# CHARGER.net
KiCad netlist of a schematic drawn in Altium Designer
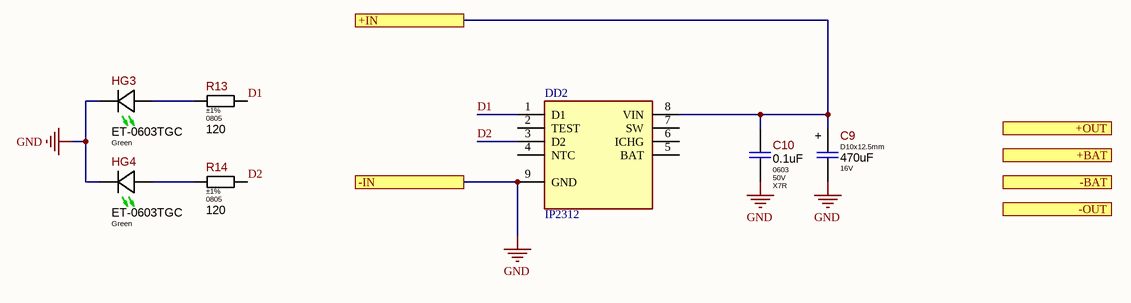
[diagram p0: CHARGER.SchDoc]

(export (version "E")
  (design (tool "Eeschema 10.0.6"))
  (components
    (comp (ref "C9")
      (value "470uF")
      (footprint "CAP-AE-PTH-100D10x125H15")
      (description "470uF 16V D10x12.5mm Electrolytic Low Impedance")
      (fields
        (field (name "PACKAGE") "D10x12.5mm")
        (field (name "VOLTAGE") "16V")
        (field (name "PART NUMBER") "EXR471M16B")
        (field (name "MANUFACTURER") "Hitano")
      )
      (libsource (lib "capacitors") (part "EXR471M16B"))
    )
    (comp (ref "C10")
      (value "0.1uF")
      (footprint "C_CERAMIC_0603_MED")
      (description "100nF 50V X7R ±10% 0603 Ceramic Capacitor RoHS")
      (fields
        (field (name "PACKAGE") "0603")
        (field (name "VOLTAGE") "50V")
        (field (name "DIELECTRIC TYPE") "X7R")
        (field (name "PART NUMBER") "CL10B104KB8NNND")
        (field (name "MANUFACTURER") "Samsung Electro-Mechanics")
      )
      (libsource (lib "capacitors") (part "CL10B104KB8NNND"))
    )
    (comp (ref "DD2") (value "IP2312") (footprint "IP2313") (libsource (lib "vitech_lib") (part "IP2312")))
    (comp (ref "HG3")
      (value "ET-0603TGC")
      (footprint "ET-0603")
      (description "Low Power LED, Green 525nm, SMD 0603, Vf 2.35V, 28.5 ~ 72mcd @ 20 mA, 120°")
      (fields
        (field (name "PART NUMBER") "ET-0603TGC")
        (field (name "COLOR") "Green")
        (field (name "MANUFACTURER") "Everlight Electronics")
      )
      (libsource (lib "opto") (part "ET-0603TGC"))
    )
    (comp (ref "HG4")
      (value "ET-0603TGC")
      (footprint "ET-0603")
      (description "Low Power LED, Green 525nm, SMD 0603, Vf 2.35V, 28.5 ~ 72mcd @ 20 mA, 120°")
      (fields
        (field (name "PART NUMBER") "ET-0603TGC")
        (field (name "COLOR") "Green")
        (field (name "MANUFACTURER") "Everlight Electronics")
      )
      (libsource (lib "opto") (part "ET-0603TGC"))
    )
    (comp (ref "R13")
      (value "120")
      (footprint "R_ANY_CHIP_0805_MED")
      (description "120 Ohms ±1%, 1/8W 0805 Thick Film Resistor")
      (fields
        (field (name "TOLERANCE") "±1%")
        (field (name "PACKAGE") "0805")
        (field (name "PART NUMBER") "RC0805FR-07120RL")
        (field (name "MANUFACTURER") "Yageo")
      )
      (libsource (lib "resistors") (part "RC0805FR-07120RL"))
    )
    (comp (ref "R14")
      (value "120")
      (footprint "R_ANY_CHIP_0805_MED")
      (description "120 Ohms ±1%, 1/8W 0805 Thick Film Resistor")
      (fields
        (field (name "TOLERANCE") "±1%")
        (field (name "PACKAGE") "0805")
        (field (name "PART NUMBER") "RC0805FR-07120RL")
        (field (name "MANUFACTURER") "Yageo")
      )
      (libsource (lib "resistors") (part "RC0805FR-07120RL"))
    )
  )
  (nets
    (net (code "2") (name "/+IN") (class "Default")
      (node (ref "C10") (pin "1") (pinfunction "1_1") (pintype "passive"))
      (node (ref "C9") (pin "1") (pinfunction "1_1") (pintype "passive"))
      (node (ref "DD2") (pin "8") (pinfunction "VIN_8") (pintype "passive"))
    )
    (net (code "6") (name "/D1") (class "Default")
      (node (ref "DD2") (pin "1") (pinfunction "D1_1") (pintype "passive"))
      (node (ref "R13") (pin "2") (pintype "passive"))
    )
    (net (code "7") (name "/D2") (class "Default")
      (node (ref "DD2") (pin "3") (pinfunction "D2_3") (pintype "passive"))
      (node (ref "R14") (pin "2") (pintype "passive"))
    )
    (net (code "8") (name "GND") (class "Default")
      (node (ref "C10") (pin "2") (pinfunction "2_2") (pintype "passive"))
      (node (ref "C9") (pin "2") (pinfunction "2_2") (pintype "passive"))
      (node (ref "DD2") (pin "9") (pinfunction "GND_9") (pintype "passive"))
      (node (ref "HG3") (pin "CA") (pinfunction "Cathode_CA") (pintype "passive"))
      (node (ref "HG4") (pin "CA") (pinfunction "Cathode_CA") (pintype "passive"))
    )
    (net (code "9") (name "Net-(HG3-Anode)") (class "Default")
      (node (ref "HG3") (pin "AN") (pinfunction "Anode_AN") (pintype "passive"))
      (node (ref "R13") (pin "1") (pintype "passive"))
    )
    (net (code "10") (name "Net-(HG4-Anode)") (class "Default")
      (node (ref "HG4") (pin "AN") (pinfunction "Anode_AN") (pintype "passive"))
      (node (ref "R14") (pin "1") (pintype "passive"))
    )
    (net (code "11") (name "unconnected-(DD2-BAT-Pad5)") (class "Default")
      (node (ref "DD2") (pin "5") (pinfunction "BAT_5") (pintype "passive"))
    )
    (net (code "12") (name "unconnected-(DD2-ICHG-Pad6)") (class "Default")
      (node (ref "DD2") (pin "6") (pinfunction "ICHG_6") (pintype "passive"))
    )
    (net (code "13") (name "unconnected-(DD2-NTC-Pad4)") (class "Default")
      (node (ref "DD2") (pin "4") (pinfunction "NTC_4") (pintype "passive"))
    )
    (net (code "14") (name "unconnected-(DD2-SW-Pad7)") (class "Default")
      (node (ref "DD2") (pin "7") (pinfunction "SW_7") (pintype "passive"))
    )
    (net (code "15") (name "unconnected-(DD2-TEST-Pad2)") (class "Default")
      (node (ref "DD2") (pin "2") (pinfunction "TEST_2") (pintype "passive"))
    )
  )
)
